# dash-dock.net
KiCad netlist of a schematic drawn in EAGLE
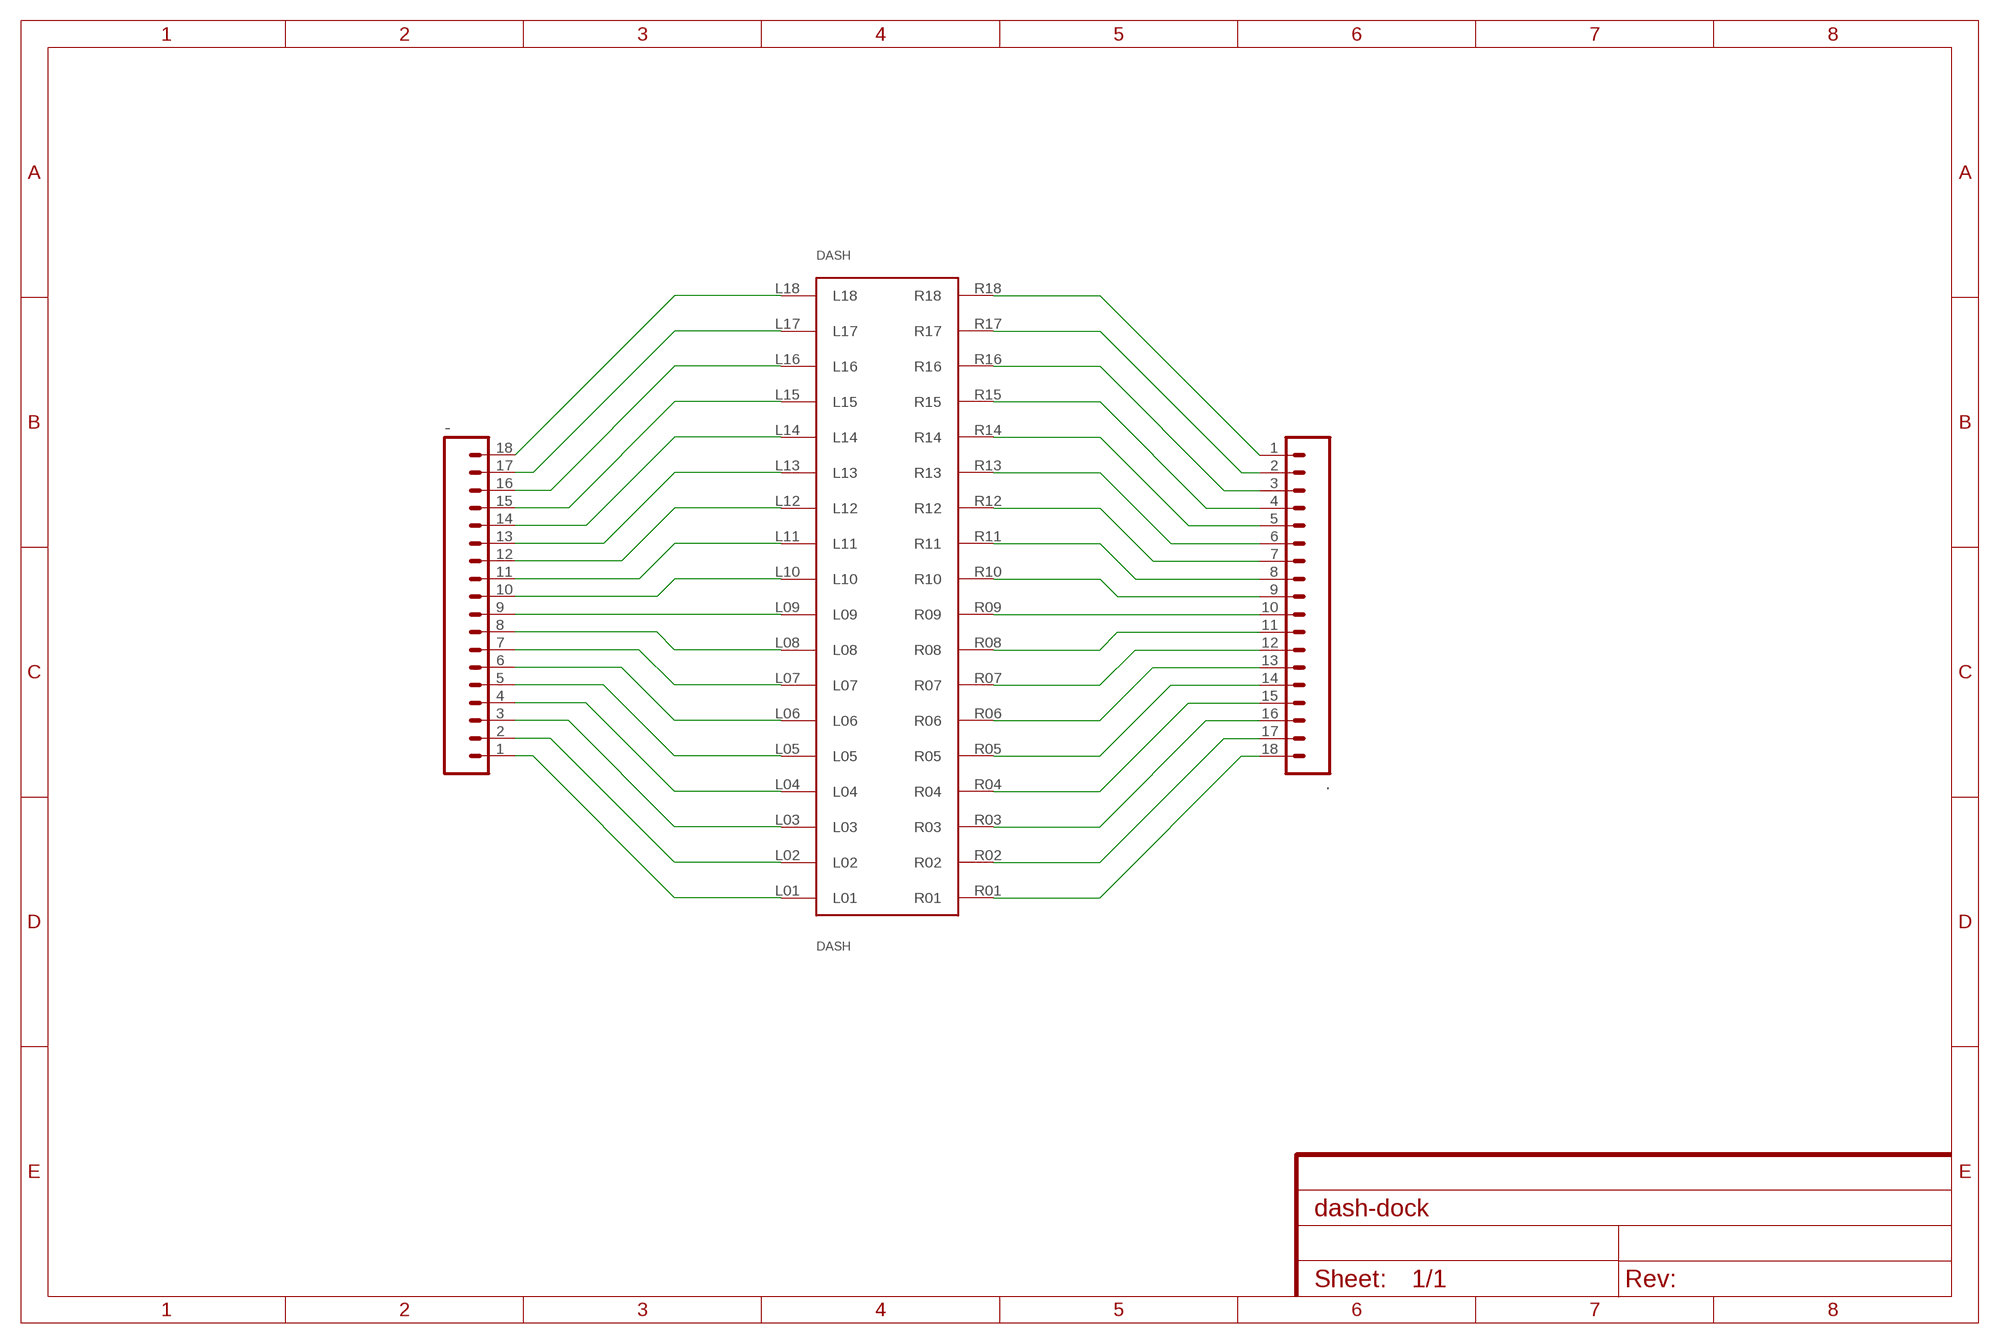
[diagram p0: schematic, sheet 1]

(export (version "E")
  (design (tool "Eeschema 10.0.6"))
  (components
    (comp (ref "-")
      (value "CONN_18")
      (footprint "eagle-import:1X18")
      (libsource (lib "eagle-import") (part "CONN_18"))
    )
    (comp (ref ".")
      (value "CONN_18")
      (footprint "eagle-import:1X18")
      (libsource (lib "eagle-import") (part "CONN_18"))
    )
    (comp (ref "DASH")
      (value "DASH")
      (footprint "eagle-import:DASH")
      (libsource (lib "eagle-import") (part "DASH"))
    )
  )
  (nets
    (net (code "1") (name "/GND") (class "Default")
      (node (ref "-") (pin "2") (pinfunction "2_2") (pintype "passive"))
      (node (ref ".") (pin "17") (pinfunction "17_17") (pintype "passive"))
      (node (ref "DASH") (pin "L02") (pinfunction "L02_L02") (pintype "bidirectional"))
      (node (ref "DASH") (pin "R02") (pinfunction "R02_R02") (pintype "bidirectional"))
    )
    (net (code "2") (name "Net-(--Pad1)") (class "Default")
      (node (ref "-") (pin "1") (pinfunction "1_1") (pintype "passive"))
      (node (ref "DASH") (pin "L01") (pinfunction "L01_L01") (pintype "bidirectional"))
    )
    (net (code "3") (name "Net-(--Pad3)") (class "Default")
      (node (ref "-") (pin "3") (pinfunction "3_3") (pintype "passive"))
      (node (ref "DASH") (pin "L03") (pinfunction "L03_L03") (pintype "bidirectional"))
    )
    (net (code "4") (name "Net-(--Pad4)") (class "Default")
      (node (ref "-") (pin "4") (pinfunction "4_4") (pintype "passive"))
      (node (ref "DASH") (pin "L04") (pinfunction "L04_L04") (pintype "bidirectional"))
    )
    (net (code "5") (name "Net-(--Pad5)") (class "Default")
      (node (ref "-") (pin "5") (pinfunction "5_5") (pintype "passive"))
      (node (ref "DASH") (pin "L05") (pinfunction "L05_L05") (pintype "bidirectional"))
    )
    (net (code "6") (name "Net-(--Pad6)") (class "Default")
      (node (ref "-") (pin "6") (pinfunction "6_6") (pintype "passive"))
      (node (ref "DASH") (pin "L06") (pinfunction "L06_L06") (pintype "bidirectional"))
    )
    (net (code "7") (name "Net-(--Pad7)") (class "Default")
      (node (ref "-") (pin "7") (pinfunction "7_7") (pintype "passive"))
      (node (ref "DASH") (pin "L07") (pinfunction "L07_L07") (pintype "bidirectional"))
    )
    (net (code "8") (name "Net-(--Pad8)") (class "Default")
      (node (ref "-") (pin "8") (pinfunction "8_8") (pintype "passive"))
      (node (ref "DASH") (pin "L08") (pinfunction "L08_L08") (pintype "bidirectional"))
    )
    (net (code "9") (name "Net-(--Pad9)") (class "Default")
      (node (ref "-") (pin "9") (pinfunction "9_9") (pintype "passive"))
      (node (ref "DASH") (pin "L09") (pinfunction "L09_L09") (pintype "bidirectional"))
    )
    (net (code "10") (name "Net-(--Pad10)") (class "Default")
      (node (ref "-") (pin "10") (pinfunction "10_10") (pintype "passive"))
      (node (ref "DASH") (pin "L10") (pinfunction "L10_L10") (pintype "bidirectional"))
    )
    (net (code "11") (name "Net-(--Pad11)") (class "Default")
      (node (ref "-") (pin "11") (pinfunction "11_11") (pintype "passive"))
      (node (ref "DASH") (pin "L11") (pinfunction "L11_L11") (pintype "bidirectional"))
    )
    (net (code "12") (name "Net-(--Pad12)") (class "Default")
      (node (ref "-") (pin "12") (pinfunction "12_12") (pintype "passive"))
      (node (ref "DASH") (pin "L12") (pinfunction "L12_L12") (pintype "bidirectional"))
    )
    (net (code "13") (name "Net-(--Pad13)") (class "Default")
      (node (ref "-") (pin "13") (pinfunction "13_13") (pintype "passive"))
      (node (ref "DASH") (pin "L13") (pinfunction "L13_L13") (pintype "bidirectional"))
    )
    (net (code "14") (name "Net-(--Pad14)") (class "Default")
      (node (ref "-") (pin "14") (pinfunction "14_14") (pintype "passive"))
      (node (ref "DASH") (pin "L14") (pinfunction "L14_L14") (pintype "bidirectional"))
    )
    (net (code "15") (name "Net-(--Pad15)") (class "Default")
      (node (ref "-") (pin "15") (pinfunction "15_15") (pintype "passive"))
      (node (ref "DASH") (pin "L15") (pinfunction "L15_L15") (pintype "bidirectional"))
    )
    (net (code "16") (name "Net-(--Pad16)") (class "Default")
      (node (ref "-") (pin "16") (pinfunction "16_16") (pintype "passive"))
      (node (ref "DASH") (pin "L16") (pinfunction "L16_L16") (pintype "bidirectional"))
    )
    (net (code "17") (name "Net-(--Pad17)") (class "Default")
      (node (ref "-") (pin "17") (pinfunction "17_17") (pintype "passive"))
      (node (ref "DASH") (pin "L17") (pinfunction "L17_L17") (pintype "bidirectional"))
    )
    (net (code "18") (name "Net-(--Pad18)") (class "Default")
      (node (ref "-") (pin "18") (pinfunction "18_18") (pintype "passive"))
      (node (ref "DASH") (pin "L18") (pinfunction "L18_L18") (pintype "bidirectional"))
    )
    (net (code "19") (name "Net-(.-Pad1)") (class "Default")
      (node (ref ".") (pin "1") (pinfunction "1_1") (pintype "passive"))
      (node (ref "DASH") (pin "R18") (pinfunction "R18_R18") (pintype "bidirectional"))
    )
    (net (code "20") (name "Net-(.-Pad2)") (class "Default")
      (node (ref ".") (pin "2") (pinfunction "2_2") (pintype "passive"))
      (node (ref "DASH") (pin "R17") (pinfunction "R17_R17") (pintype "bidirectional"))
    )
    (net (code "21") (name "Net-(.-Pad3)") (class "Default")
      (node (ref ".") (pin "3") (pinfunction "3_3") (pintype "passive"))
      (node (ref "DASH") (pin "R16") (pinfunction "R16_R16") (pintype "bidirectional"))
    )
    (net (code "22") (name "Net-(.-Pad4)") (class "Default")
      (node (ref ".") (pin "4") (pinfunction "4_4") (pintype "passive"))
      (node (ref "DASH") (pin "R15") (pinfunction "R15_R15") (pintype "bidirectional"))
    )
    (net (code "23") (name "Net-(.-Pad5)") (class "Default")
      (node (ref ".") (pin "5") (pinfunction "5_5") (pintype "passive"))
      (node (ref "DASH") (pin "R14") (pinfunction "R14_R14") (pintype "bidirectional"))
    )
    (net (code "24") (name "Net-(.-Pad6)") (class "Default")
      (node (ref ".") (pin "6") (pinfunction "6_6") (pintype "passive"))
      (node (ref "DASH") (pin "R13") (pinfunction "R13_R13") (pintype "bidirectional"))
    )
    (net (code "25") (name "Net-(.-Pad7)") (class "Default")
      (node (ref ".") (pin "7") (pinfunction "7_7") (pintype "passive"))
      (node (ref "DASH") (pin "R12") (pinfunction "R12_R12") (pintype "bidirectional"))
    )
    (net (code "26") (name "Net-(.-Pad8)") (class "Default")
      (node (ref ".") (pin "8") (pinfunction "8_8") (pintype "passive"))
      (node (ref "DASH") (pin "R11") (pinfunction "R11_R11") (pintype "bidirectional"))
    )
    (net (code "27") (name "Net-(.-Pad9)") (class "Default")
      (node (ref ".") (pin "9") (pinfunction "9_9") (pintype "passive"))
      (node (ref "DASH") (pin "R10") (pinfunction "R10_R10") (pintype "bidirectional"))
    )
    (net (code "28") (name "Net-(.-Pad10)") (class "Default")
      (node (ref ".") (pin "10") (pinfunction "10_10") (pintype "passive"))
      (node (ref "DASH") (pin "R09") (pinfunction "R09_R09") (pintype "bidirectional"))
    )
    (net (code "29") (name "Net-(.-Pad11)") (class "Default")
      (node (ref ".") (pin "11") (pinfunction "11_11") (pintype "passive"))
      (node (ref "DASH") (pin "R08") (pinfunction "R08_R08") (pintype "bidirectional"))
    )
    (net (code "30") (name "Net-(.-Pad12)") (class "Default")
      (node (ref ".") (pin "12") (pinfunction "12_12") (pintype "passive"))
      (node (ref "DASH") (pin "R07") (pinfunction "R07_R07") (pintype "bidirectional"))
    )
    (net (code "31") (name "Net-(.-Pad13)") (class "Default")
      (node (ref ".") (pin "13") (pinfunction "13_13") (pintype "passive"))
      (node (ref "DASH") (pin "R06") (pinfunction "R06_R06") (pintype "bidirectional"))
    )
    (net (code "32") (name "Net-(.-Pad14)") (class "Default")
      (node (ref ".") (pin "14") (pinfunction "14_14") (pintype "passive"))
      (node (ref "DASH") (pin "R05") (pinfunction "R05_R05") (pintype "bidirectional"))
    )
    (net (code "33") (name "Net-(.-Pad15)") (class "Default")
      (node (ref ".") (pin "15") (pinfunction "15_15") (pintype "passive"))
      (node (ref "DASH") (pin "R04") (pinfunction "R04_R04") (pintype "bidirectional"))
    )
    (net (code "34") (name "Net-(.-Pad16)") (class "Default")
      (node (ref ".") (pin "16") (pinfunction "16_16") (pintype "passive"))
      (node (ref "DASH") (pin "R03") (pinfunction "R03_R03") (pintype "bidirectional"))
    )
    (net (code "35") (name "Net-(.-Pad18)") (class "Default")
      (node (ref ".") (pin "18") (pinfunction "18_18") (pintype "passive"))
      (node (ref "DASH") (pin "R01") (pinfunction "R01_R01") (pintype "bidirectional"))
    )
  )
)
